# Top.net
KiCad netlist of a schematic drawn in Altium Designer
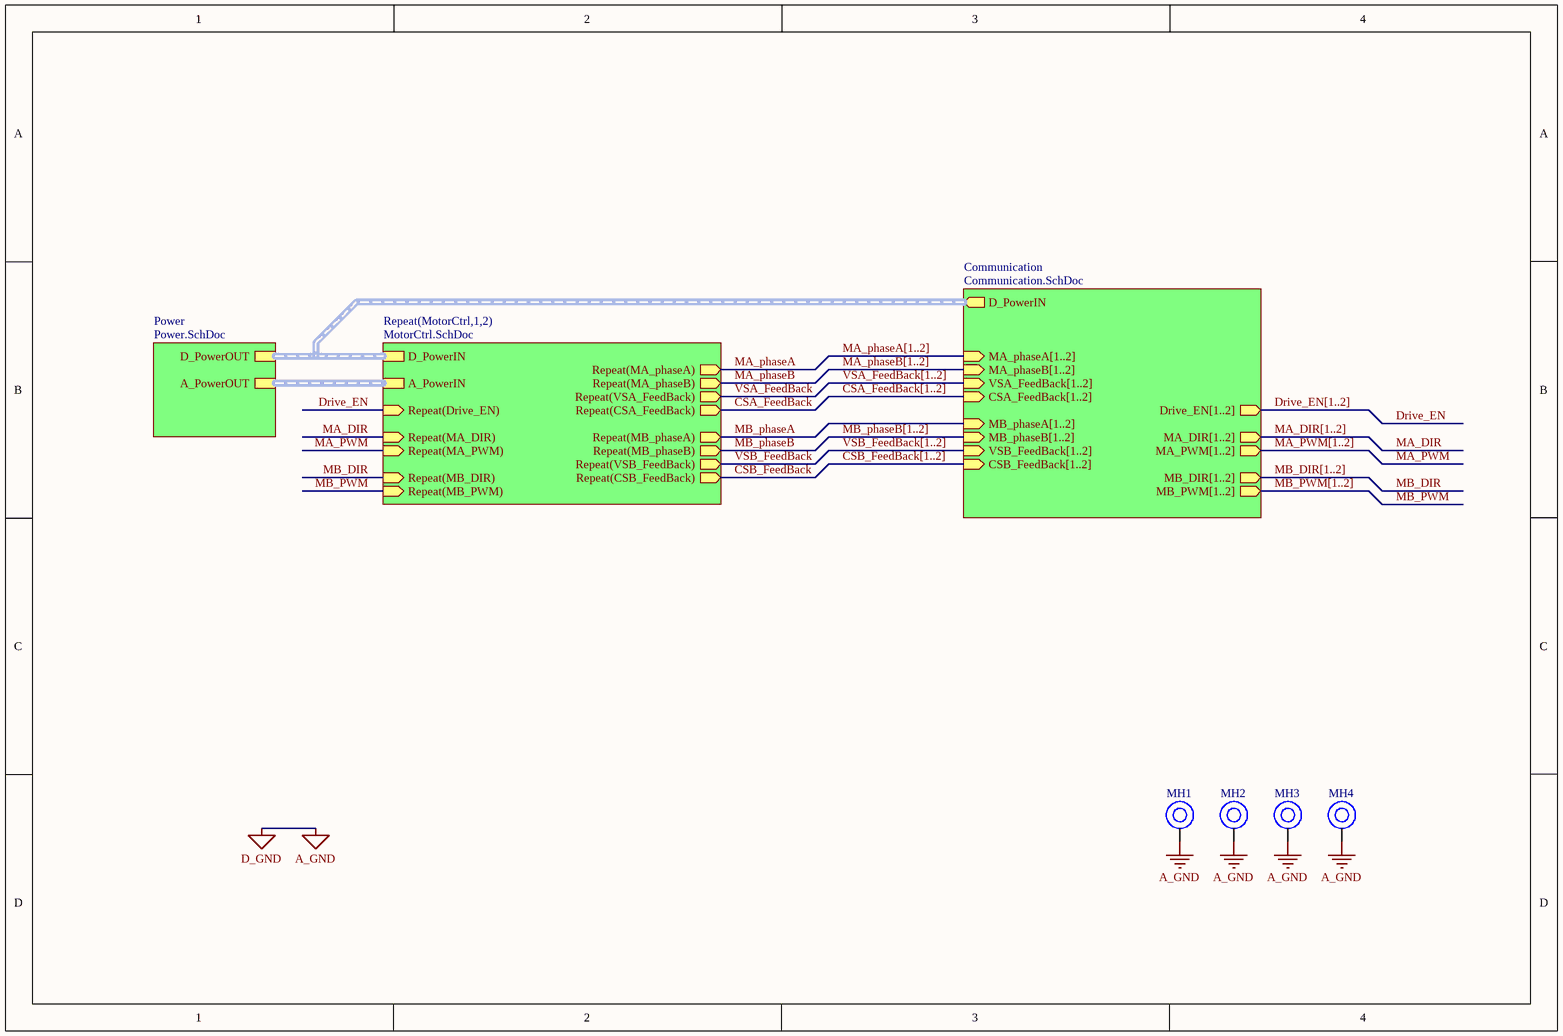
[diagram p0: Top.SchDoc]

(export (version "E")
  (design (tool "Eeschema 10.0.6"))
  (components
    (comp (ref "MH1") (value "M3 Hole") (footprint "OWMR:M3 Hole") (libsource (lib "OWMR") (part "M3_Hole")))
    (comp (ref "MH2") (value "M3 Hole") (footprint "OWMR:M3 Hole") (libsource (lib "OWMR") (part "M3_Hole")))
    (comp (ref "MH3") (value "M3 Hole") (footprint "OWMR:M3 Hole") (libsource (lib "OWMR") (part "M3_Hole")))
    (comp (ref "MH4") (value "M3 Hole") (footprint "OWMR:M3 Hole") (libsource (lib "OWMR") (part "M3_Hole")))
  )
  (nets
    (net (code "53") (name "A_GND") (class "Default")
      (node (ref "MH1") (pin "1") (pintype "passive"))
      (node (ref "MH2") (pin "1") (pintype "passive"))
      (node (ref "MH3") (pin "1") (pintype "passive"))
      (node (ref "MH4") (pin "1") (pintype "passive"))
    )
  )
)
